# ESP32.net
KiCad netlist of a schematic drawn in Altium Designer
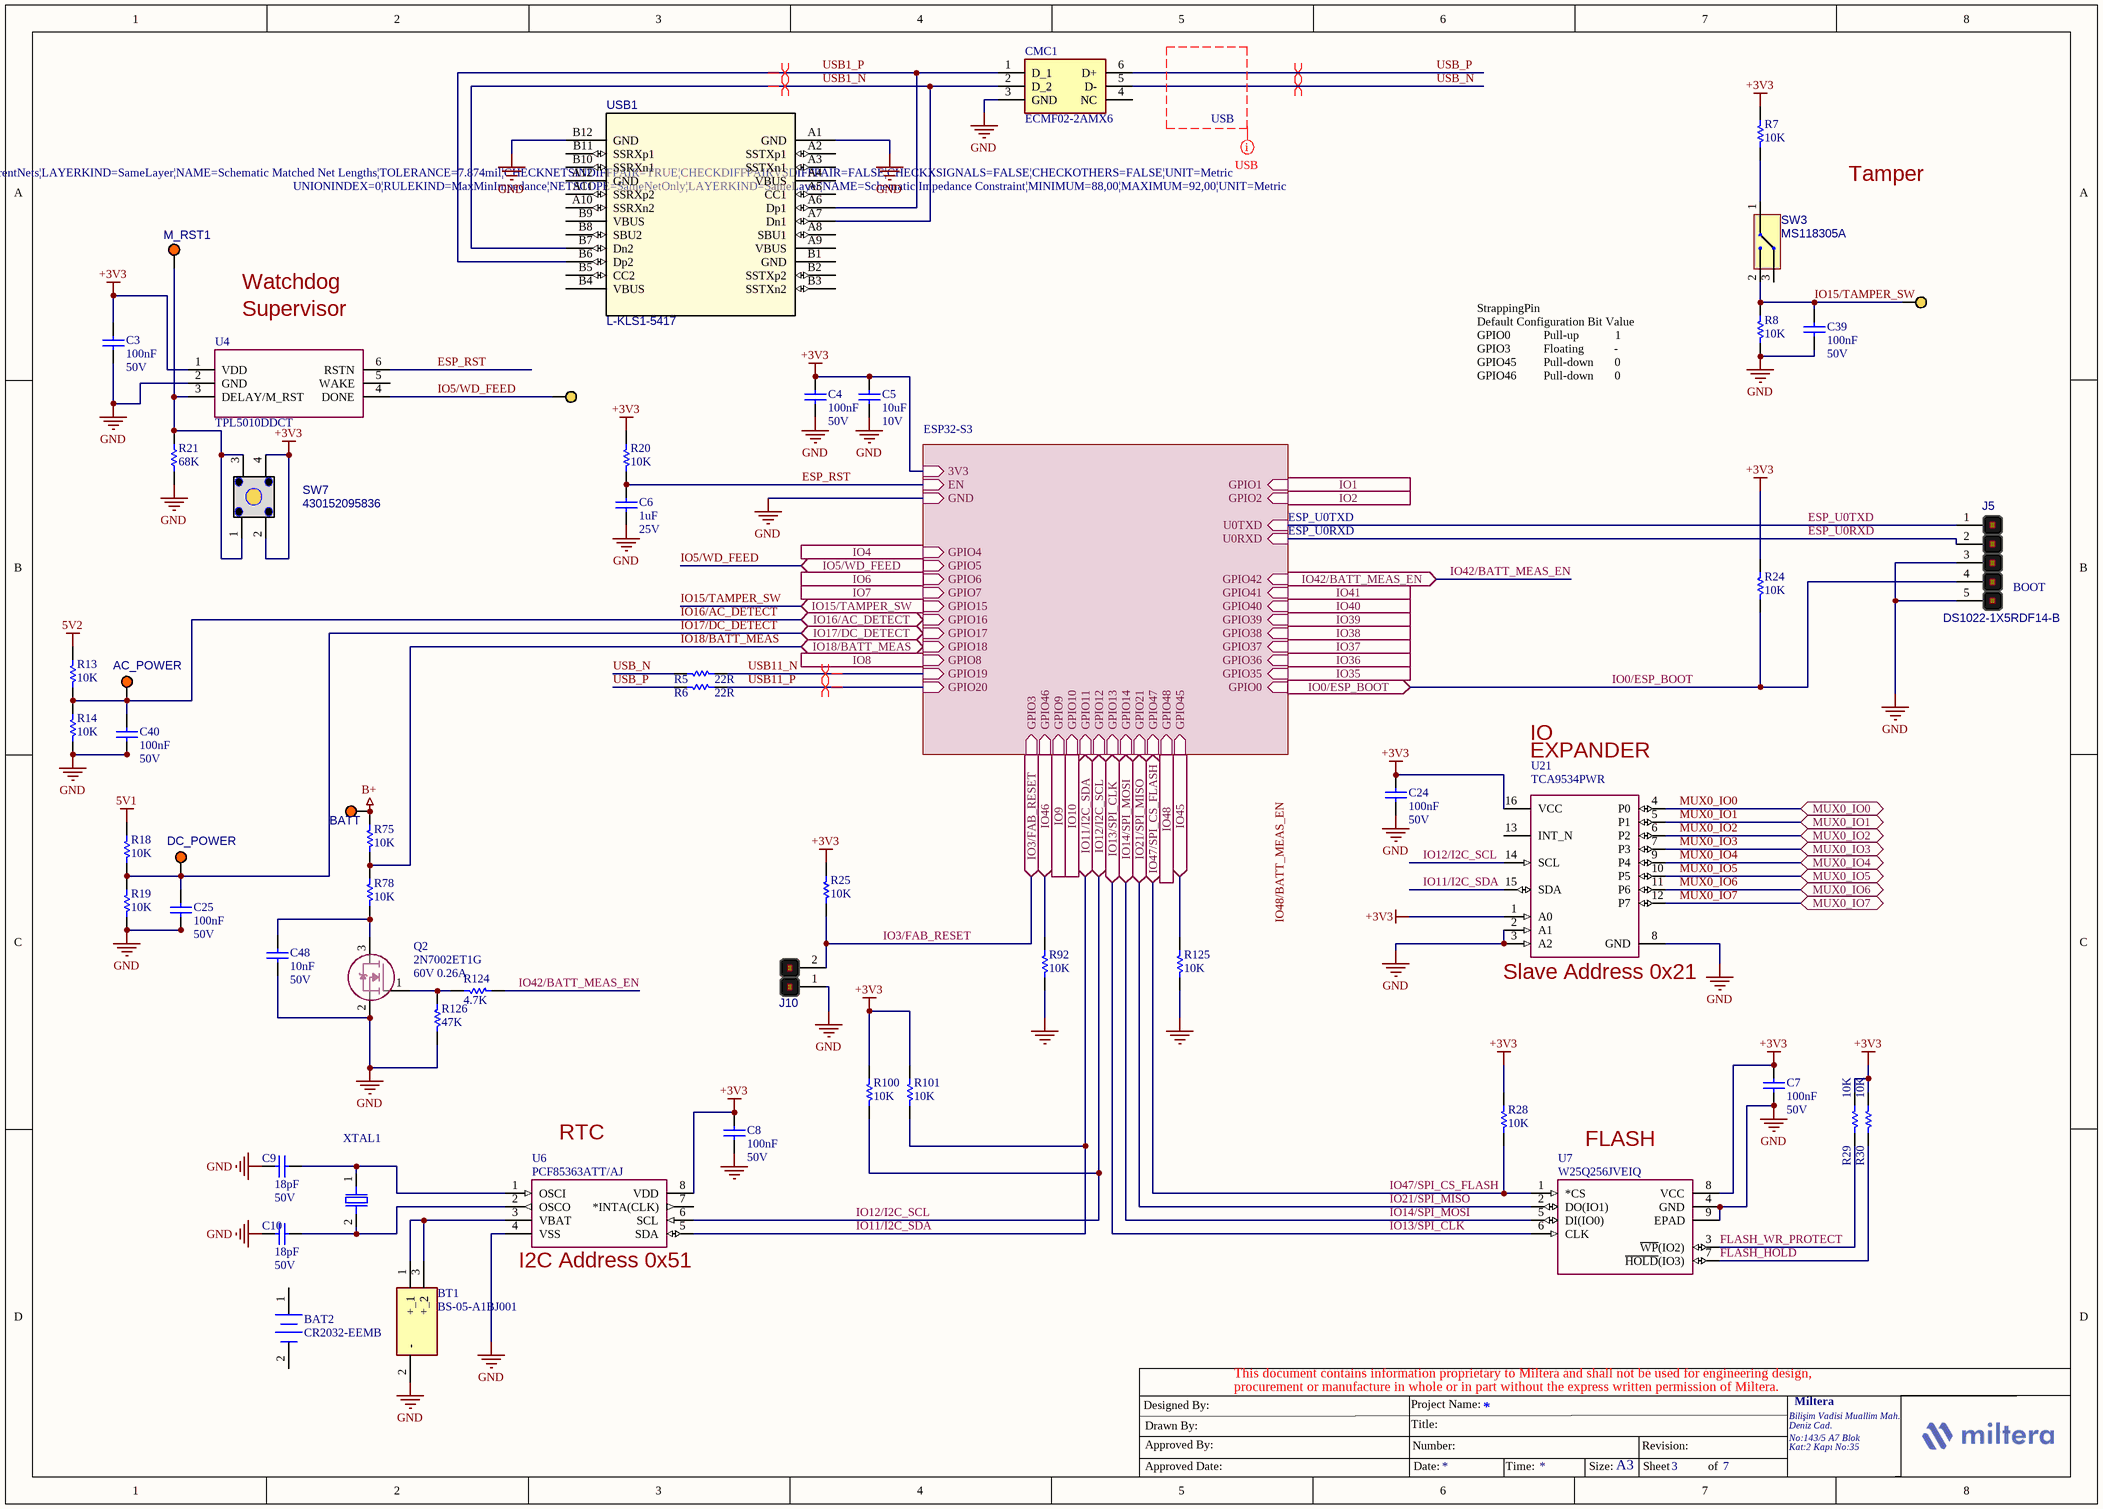
[diagram p0: ESP32.SchDoc]

(export (version "E")
  (design (tool "Eeschema 10.0.6"))
  (components
    (comp (ref "AC_POWER")
      (value "L-KLS8-TP5003")
      (footprint "TEST_POINT_ORANGE")
      (description "PC TEST POINT MINIATURE ORANGE 2.54MMX4.60MM")
      (fields (field (name "MANUFACTURER") "KLS ELECTRONIC"))
      (libsource (lib "Hardware_Fasteners") (part "5003"))
    )
    (comp (ref "BAT2")
      (value "CR2032-EEMB")
      (description "BATTERY 3V 210mA PINSIZ EEMB")
      (fields (field (name "MANUFACTURER") "EEMB"))
      (libsource (lib "open-components") (part "BAT"))
    )
    (comp (ref "BATT")
      (value "L-KLS8-TP5003")
      (footprint "TEST_POINT_ORANGE")
      (description "PC TEST POINT MINIATURE ORANGE 2.54MMX4.60MM")
      (fields (field (name "MANUFACTURER") "KLS ELECTRONIC"))
      (libsource (lib "Hardware_Fasteners") (part "5003"))
    )
    (comp (ref "BT1")
      (value "BS-05-A1BJ001")
      (footprint "SamacSys:17754851")
      (description "BATTERY HOLDER COIN CR2032 TH")
      (fields (field (name "MANUFACTURER") "MYOUNG"))
      (libsource (lib "*") (part "1775485-1"))
    )
    (comp (ref "C3")
      (value "100nF")
      (footprint "CAP_0603")
      (description "CAP CER 100nF 50VDC %10 X7R SMD")
      (fields
        (field (name "VOLTAGE") "50V")
        (field (name "MANUFACTURER") "Samsung")
        (field (name "MANUFACTURER PART NUMBER") "CL10B104KB8NNNL")
      )
      (libsource (lib "open-components") (part "CAP"))
    )
    (comp (ref "C4")
      (value "100nF")
      (footprint "CAP_0603")
      (description "CAP CER 100nF 50VDC %10 X7R SMD")
      (fields
        (field (name "VOLTAGE") "50V")
        (field (name "MANUFACTURER") "Samsung")
        (field (name "MANUFACTURER PART NUMBER") "CL10B104KB8NNNL")
      )
      (libsource (lib "open-components") (part "CAP"))
    )
    (comp (ref "C5")
      (value "10uF")
      (footprint "CAP_0603")
      (description "MLCC (1608) 0603 10uF 10VDC ±20% X5R")
      (fields
        (field (name "VOLTAGE") "10V")
        (field (name "MANUFACTURER") "Samsung")
        (field (name "MANUFACTURER PART NUMBER") "CL10A106MP8NNNC")
      )
      (libsource (lib "open-components") (part "CAP"))
    )
    (comp (ref "C6")
      (value "1uF")
      (footprint "CAP_0603")
      (description "CAP CER 1UF 25VDC %10 X5R SMD")
      (fields
        (field (name "VOLTAGE") "25V")
        (field (name "MANUFACTURER") "Samsung")
        (field (name "MANUFACTURER PART NUMBER") "CL10A105KA8NNNC")
      )
      (libsource (lib "open-components") (part "CAP"))
    )
    (comp (ref "C7")
      (value "100nF")
      (footprint "CAP_0603")
      (description "CAP CER 100nF 50VDC %10 X7R SMD")
      (fields
        (field (name "VOLTAGE") "50V")
        (field (name "MANUFACTURER") "Samsung")
        (field (name "MANUFACTURER PART NUMBER") "CL10B104KB8NNNL")
      )
      (libsource (lib "open-components") (part "CAP"))
    )
    (comp (ref "C8")
      (value "100nF")
      (footprint "CAP_0603")
      (description "CAP CER 100nF 50VDC %10 X7R SMD")
      (fields
        (field (name "VOLTAGE") "50V")
        (field (name "MANUFACTURER") "Samsung")
        (field (name "MANUFACTURER PART NUMBER") "CL10B104KB8NNNL")
      )
      (libsource (lib "open-components") (part "CAP"))
    )
    (comp (ref "C9")
      (value "18pF")
      (footprint "CAP_0603")
      (description "MLCC (1608) 0603 18pF 50VDC ±5% C0G (NP0)")
      (fields
        (field (name "VOLTAGE") "50V")
        (field (name "MANUFACTURER") "Samsung")
        (field (name "MANUFACTURER PART NUMBER") "CL10C180JB8NNNC")
      )
      (libsource (lib "open-components") (part "CAP"))
    )
    (comp (ref "C10")
      (value "18pF")
      (footprint "CAP_0603")
      (description "MLCC (1608) 0603 18pF 50VDC ±5% C0G (NP0)")
      (fields
        (field (name "VOLTAGE") "50V")
        (field (name "MANUFACTURER") "Samsung")
        (field (name "MANUFACTURER PART NUMBER") "CL10C180JB8NNNC")
      )
      (libsource (lib "open-components") (part "CAP"))
    )
    (comp (ref "C24")
      (value "100nF")
      (footprint "CAP_0603")
      (description "CAP CER 100nF 50VDC %10 X7R SMD")
      (fields
        (field (name "VOLTAGE") "50V")
        (field (name "MANUFACTURER") "Samsung")
        (field (name "MANUFACTURER PART NUMBER") "CL10B104KB8NNNL")
      )
      (libsource (lib "open-components") (part "CAP"))
    )
    (comp (ref "C25")
      (value "100nF")
      (footprint "CAP_0603")
      (description "CAP CER 100nF 50VDC %10 X7R SMD")
      (fields
        (field (name "VOLTAGE") "50V")
        (field (name "MANUFACTURER") "Samsung")
        (field (name "MANUFACTURER PART NUMBER") "CL10B104KB8NNNL")
      )
      (libsource (lib "open-components") (part "CAP"))
    )
    (comp (ref "C39")
      (value "100nF")
      (footprint "CAP_0603")
      (description "CAP CER 100nF 50VDC %10 X7R SMD")
      (fields
        (field (name "VOLTAGE") "50V")
        (field (name "MANUFACTURER") "Samsung")
        (field (name "MANUFACTURER PART NUMBER") "CL10B104KB8NNNL")
      )
      (libsource (lib "open-components") (part "CAP"))
    )
    (comp (ref "C40")
      (value "100nF")
      (footprint "CAP_0603")
      (description "CAP CER 100nF 50VDC %10 X7R SMD")
      (fields
        (field (name "VOLTAGE") "50V")
        (field (name "MANUFACTURER") "Samsung")
        (field (name "MANUFACTURER PART NUMBER") "CL10B104KB8NNNL")
      )
      (libsource (lib "open-components") (part "CAP"))
    )
    (comp (ref "C48")
      (value "10nF")
      (footprint "CAP_0603")
      (description "MLCC (1608) 0603 10nF 50VDC ±10% X7R")
      (fields
        (field (name "VOLTAGE") "50V")
        (field (name "MANUFACTURER") "SAMSUNG")
        (field (name "MANUFACTURER PART NUMBER") "CL10B103KB8NNNC")
      )
      (libsource (lib "open-components") (part "CAP"))
    )
    (comp (ref "CMC1")
      (value "ECMF02-2AMX6")
      (footprint "SamacSys:SON50P150X170X55-6N-D")
      (description "CHOKE COMMON MODE CMC 200MA 2LN 2.5 OHM SMD")
      (fields (field (name "MANUFACTURER") "STMicroelectronics"))
      (libsource (lib "*") (part "ECMF02-2AMX6"))
    )
    (comp (ref "DC_POWER")
      (value "L-KLS8-TP5003")
      (footprint "TEST_POINT_ORANGE")
      (description "PC TEST POINT MINIATURE ORANGE 2.54MMX4.60MM")
      (fields (field (name "MANUFACTURER") "KLS ELECTRONIC"))
      (libsource (lib "Hardware_Fasteners") (part "5003"))
    )
    (comp (ref "J5")
      (value "DS1022-1X5RDF14-B")
      (footprint "PIN_HEADER_MALE_TH_1x5_2.54mm")
      (description "PIN HEADER 5PIN(1x5) 2.54mm THT R/A")
      (fields (field (name "MANUFACTURER") "CONNFLY"))
      (libsource (lib "Connectors") (part "2355172-5"))
    )
    (comp (ref "J10")
      (value "L-KLS1-207-1-02-S")
      (footprint "PIN HEADER 2PIN(1x2) 2.54mm THT V/T")
      (description "PIN HEADER 2PIN(1x2) 2.54mm THT V/T")
      (fields (field (name "MANUFACTURER") "KLS ELECTRONIC"))
      (libsource (lib "MTOSOS_R02") (part "L-KLS1-207-1-02-S"))
    )
    (comp (ref "M_RST1")
      (value "L-KLS8-TP5003")
      (footprint "TEST_POINT_ORANGE")
      (description "PC TEST POINT MINIATURE ORANGE 2.54MMX4.60MM")
      (fields (field (name "MANUFACTURER") "KLS ELECTRONIC"))
      (libsource (lib "Hardware_Fasteners") (part "5003"))
    )
    (comp (ref "Q2")
      (value "2N7002ET1G")
      (footprint "SOT23")
      (description "MOSFET N-CH 60V 260mA SOT-23")
      (fields (field (name "MANUFACTURER") "On Semiconductor") (field (name "ALTIUM_VALUE") "60V 0.26A"))
      (libsource (lib "Semiconductors") (part "2N7002ET1G"))
    )
    (comp (ref "R5")
      (value "22R")
      (footprint "RES_0603")
      (description "RES 0603 22 Ohms 5% 1/10W-S 100PPM")
      (fields
        (field (name "MANUFACTURER") "ROYALOHM")
        (field (name "MANUFACTURER PART NUMBER") "0603SAJ0220T5E")
      )
      (libsource (lib "open-components") (part "RES"))
    )
    (comp (ref "R6")
      (value "22R")
      (footprint "RES_0603")
      (description "RES 0603 22 Ohms 5% 1/10W-S 100PPM")
      (fields
        (field (name "MANUFACTURER") "ROYALOHM")
        (field (name "MANUFACTURER PART NUMBER") "0603SAJ0220T5E")
      )
      (libsource (lib "open-components") (part "RES"))
    )
    (comp (ref "R7")
      (value "10K")
      (footprint "RES_0603")
      (description "RES 0603 10k Ohms %1 1/10W 100PPM")
      (fields
        (field (name "MANUFACTURER") "ROYALOHM")
        (field (name "MANUFACTURER PART NUMBER") "0603SAF1002T5E")
      )
      (libsource (lib "open-components") (part "RES"))
    )
    (comp (ref "R8")
      (value "10K")
      (footprint "RES_0603")
      (description "RES 0603 10k Ohms %1 1/10W 100PPM")
      (fields
        (field (name "MANUFACTURER") "ROYALOHM")
        (field (name "MANUFACTURER PART NUMBER") "0603SAF1002T5E")
      )
      (libsource (lib "open-components") (part "RES"))
    )
    (comp (ref "R13")
      (value "10K")
      (footprint "RES_0603")
      (description "RES 0603 10k Ohms %1 1/10W 100PPM")
      (fields
        (field (name "MANUFACTURER") "ROYALOHM")
        (field (name "MANUFACTURER PART NUMBER") "0603SAF1002T5E")
      )
      (libsource (lib "open-components") (part "RES"))
    )
    (comp (ref "R14")
      (value "10K")
      (footprint "RES_0603")
      (description "RES 0603 10k Ohms %1 1/10W 100PPM")
      (fields
        (field (name "MANUFACTURER") "ROYALOHM")
        (field (name "MANUFACTURER PART NUMBER") "0603SAF1002T5E")
      )
      (libsource (lib "open-components") (part "RES"))
    )
    (comp (ref "R18")
      (value "10K")
      (footprint "RES_0603")
      (description "RES 0603 10k Ohms %1 1/10W 100PPM")
      (fields
        (field (name "MANUFACTURER") "ROYALOHM")
        (field (name "MANUFACTURER PART NUMBER") "0603SAF1002T5E")
      )
      (libsource (lib "open-components") (part "RES"))
    )
    (comp (ref "R19")
      (value "10K")
      (footprint "RES_0603")
      (description "RES 0603 10k Ohms %1 1/10W 100PPM")
      (fields
        (field (name "MANUFACTURER") "ROYALOHM")
        (field (name "MANUFACTURER PART NUMBER") "0603SAF1002T5E")
      )
      (libsource (lib "open-components") (part "RES"))
    )
    (comp (ref "R20")
      (value "10K")
      (footprint "RES_0603")
      (description "RES 0603 10k Ohms %1 1/10W 100PPM")
      (fields
        (field (name "MANUFACTURER") "ROYALOHM")
        (field (name "MANUFACTURER PART NUMBER") "0603SAF1002T5E")
      )
      (libsource (lib "open-components") (part "RES"))
    )
    (comp (ref "R21")
      (value "68K")
      (footprint "RES_0603")
      (description "RES. 0603 68K Ohms 1% 1/10W-S 100PPM")
      (fields
        (field (name "MANUFACTURER") "ROYALOHM")
        (field (name "MANUFACTURER PART NUMBER") "0603SAF6802T5E")
      )
      (libsource (lib "open-components") (part "RES"))
    )
    (comp (ref "R24")
      (value "10K")
      (footprint "RES_0603")
      (description "RES 0603 10k Ohms %1 1/10W 100PPM")
      (fields
        (field (name "MANUFACTURER") "ROYALOHM")
        (field (name "MANUFACTURER PART NUMBER") "0603SAF1002T5E")
      )
      (libsource (lib "open-components") (part "RES"))
    )
    (comp (ref "R25")
      (value "10K")
      (footprint "RES_0603")
      (description "RES 0603 10k Ohms %1 1/10W 100PPM")
      (fields
        (field (name "MANUFACTURER") "ROYALOHM")
        (field (name "MANUFACTURER PART NUMBER") "0603SAF1002T5E")
      )
      (libsource (lib "open-components") (part "RES"))
    )
    (comp (ref "R28")
      (value "10K")
      (footprint "RES_0603")
      (description "RES 0603 10k Ohms %1 1/10W 100PPM")
      (fields
        (field (name "MANUFACTURER") "ROYALOHM")
        (field (name "MANUFACTURER PART NUMBER") "0603SAF1002T5E")
      )
      (libsource (lib "open-components") (part "RES"))
    )
    (comp (ref "R29")
      (value "10K")
      (footprint "RES_0603")
      (description "RES 0603 10k Ohms %1 1/10W 100PPM")
      (fields
        (field (name "MANUFACTURER") "ROYALOHM")
        (field (name "MANUFACTURER PART NUMBER") "0603SAF1002T5E")
      )
      (libsource (lib "open-components") (part "RES"))
    )
    (comp (ref "R30")
      (value "10K")
      (footprint "RES_0603")
      (description "RES 0603 10k Ohms %1 1/10W 100PPM")
      (fields
        (field (name "MANUFACTURER") "ROYALOHM")
        (field (name "MANUFACTURER PART NUMBER") "0603SAF1002T5E")
      )
      (libsource (lib "open-components") (part "RES"))
    )
    (comp (ref "R75")
      (value "10K")
      (footprint "RES_0603")
      (description "RES 0603 10k Ohms %1 1/10W 100PPM")
      (fields
        (field (name "MANUFACTURER") "ROYALOHM")
        (field (name "MANUFACTURER PART NUMBER") "0603SAF1002T5E")
      )
      (libsource (lib "open-components") (part "RES"))
    )
    (comp (ref "R78")
      (value "10K")
      (footprint "RES_0603")
      (description "RES 0603 10k Ohms %1 1/10W 100PPM")
      (fields
        (field (name "MANUFACTURER") "ROYALOHM")
        (field (name "MANUFACTURER PART NUMBER") "0603SAF1002T5E")
      )
      (libsource (lib "open-components") (part "RES"))
    )
    (comp (ref "R92")
      (value "10K")
      (footprint "RES_0603")
      (description "RES 0603 10k Ohms %1 1/10W 100PPM")
      (fields
        (field (name "MANUFACTURER") "ROYALOHM")
        (field (name "MANUFACTURER PART NUMBER") "0603SAF1002T5E")
      )
      (libsource (lib "open-components") (part "RES"))
    )
    (comp (ref "R100")
      (value "10K")
      (footprint "RES_0603")
      (description "RES 0603 10k Ohms %1 1/10W 100PPM")
      (fields
        (field (name "MANUFACTURER") "ROYALOHM")
        (field (name "MANUFACTURER PART NUMBER") "0603SAF1002T5E")
      )
      (libsource (lib "open-components") (part "RES"))
    )
    (comp (ref "R101")
      (value "10K")
      (footprint "RES_0603")
      (description "RES 0603 10k Ohms %1 1/10W 100PPM")
      (fields
        (field (name "MANUFACTURER") "ROYALOHM")
        (field (name "MANUFACTURER PART NUMBER") "0603SAF1002T5E")
      )
      (libsource (lib "open-components") (part "RES"))
    )
    (comp (ref "R124")
      (value "4.7K")
      (footprint "RES_0603")
      (description "RES 0603 4.7k Ohms %1 1/10W 100PPM")
      (fields
        (field (name "MANUFACTURER") "ROYALOHM")
        (field (name "MANUFACTURER PART NUMBER") "0603SAF4701T5E")
      )
      (libsource (lib "open-components") (part "RES"))
    )
    (comp (ref "R125")
      (value "10K")
      (footprint "RES_0603")
      (description "RES 0603 10k Ohms %1 1/10W 100PPM")
      (fields
        (field (name "MANUFACTURER") "ROYALOHM")
        (field (name "MANUFACTURER PART NUMBER") "0603SAF1002T5E")
      )
      (libsource (lib "open-components") (part "RES"))
    )
    (comp (ref "R126")
      (value "47K")
      (footprint "RES_0603")
      (description "RES 0603 47K Ohms 1% 1/10W-S 100PPM")
      (fields
        (field (name "MANUFACTURER") "ROYALOHM")
        (field (name "MANUFACTURER PART NUMBER") "0603SAF4702T5E")
      )
      (libsource (lib "open-components") (part "RES"))
    )
    (comp (ref "SW3")
      (value "MS118305A")
      (footprint "MS118305A")
      (description "SWITCH MICRO SPDT 100mA 30VDC 25gF")
      (fields (field (name "MANUFACTURER") "LITTELFUSE-C&K"))
      (libsource (lib "Schlib1") (part "MS118305A"))
    )
    (comp (ref "SW7")
      (value "430152095836")
      (footprint "SMD_TACT_SW_6x6_9.50mm")
      (description "SWITCH TACT 6.2x6.2 9.50mm 360gF SMT V/T")
      (fields (field (name "MANUFACTURER") "Würth Elektronik"))
      (libsource (lib "Electromechanical") (part "430152095836"))
    )
    (comp (ref "TAMPER_SW")
      (value "L-KLS8-TP5004")
      (footprint "TEST_POINT_YELLOW")
      (description "PC TEST POINT MINIATURE YELLOW 2.54MMX4.60MM")
      (fields (field (name "MANUFACTURER") "KLS ELECTRONIC"))
      (libsource (lib "Hardware_Fasteners") (part "5004"))
    )
    (comp (ref "U4")
      (value "TPL5010DDCT")
      (footprint "SOT95P280X110-6N")
      (description "IC OSC PROG TIMER TSOT23-6")
      (fields (field (name "MANUFACTURER") "Texas Instruments"))
      (libsource (lib "Schlib1") (part "TPL5010DDCT"))
    )
    (comp (ref "U6")
      (value "PCF85363ATT/AJ")
      (footprint "TSSOP8_SOT505-1_NXP")
      (description "IC RTC CLK/CALENDAR I2C 8TSSOP")
      (fields (field (name "MANUFACTURER") "NXP USA Inc."))
      (libsource (lib "Schlib1") (part "PCF85363ATT/AJ"))
    )
    (comp (ref "U7")
      (value "W25Q256JVEIQ")
      (footprint "8-WSON (8x6)")
      (description "IC FLASH 256MBIT SPI/QUAD 8WSON")
      (fields (field (name "MANUFACTURER") "Winbond Electronics"))
      (libsource (lib "Schlib1") (part "W25Q256JVEIQ"))
    )
    (comp (ref "U21")
      (value "TCA9534PWR")
      (footprint "16-TSSOP")
      (description "IC XPNDR 400KHZ I2C 16TSSOP")
      (fields (field (name "MANUFACTURER") "Texas Instruments"))
      (libsource (lib "Schlib1") (part "TCA9534PWR"))
    )
    (comp (ref "USB1")
      (value "L-KLS1-5417")
      (footprint "217C-AA01_ATT")
      (description "CONNECTOR USB 14P USB FEMALE SOCKET C TYPE")
      (fields (field (name "MANUFACTURER") "KLS ELECTRONIC"))
      (libsource (lib "MTOSOS_R02") (part "L-KLS1-5461"))
    )
    (comp (ref "WD_FEED1")
      (value "L-KLS8-TP5004")
      (footprint "TEST_POINT_YELLOW")
      (description "PC TEST POINT MINIATURE YELLOW 2.54MMX4.60MM")
      (fields (field (name "MANUFACTURER") "KLS ELECTRONIC"))
      (libsource (lib "Hardware_Fasteners") (part "5004"))
    )
    (comp (ref "XTAL1")
      (value "Crystal_2pin")
      (footprint "XTAL_3x8")
      (description "CRYSTAL 32.768KHZ 12.5PF 5ppm 3x8")
      (fields
        (field (name "MANUFACTURER PART NUMBER") "R38-32.768-12.5-EXT-5PPM")
        (field (name "MANUFACTURER") "Raltron")
      )
      (libsource (lib "open-components") (part "Crystal_2pin"))
    )
  )
  (nets
    (net (code "1") (name "+3V3") (class "Default")
      (node (ref "C24") (pin "1") (pinfunction "1_1") (pintype "passive"))
      (node (ref "C3") (pin "1") (pinfunction "1_1") (pintype "passive"))
      (node (ref "C4") (pin "1") (pinfunction "1_1") (pintype "passive"))
      (node (ref "C5") (pin "1") (pinfunction "1_1") (pintype "passive"))
      (node (ref "C7") (pin "1") (pinfunction "1_1") (pintype "passive"))
      (node (ref "C8") (pin "1") (pinfunction "1_1") (pintype "passive"))
      (node (ref "R100") (pin "1") (pinfunction "1_1") (pintype "passive"))
      (node (ref "R101") (pin "1") (pinfunction "1_1") (pintype "passive"))
      (node (ref "R20") (pin "1") (pinfunction "1_1") (pintype "passive"))
      (node (ref "R24") (pin "1") (pinfunction "1_1") (pintype "passive"))
      (node (ref "R25") (pin "1") (pinfunction "1_1") (pintype "passive"))
      (node (ref "R28") (pin "1") (pinfunction "1_1") (pintype "passive"))
      (node (ref "R29") (pin "1") (pinfunction "1_1") (pintype "passive"))
      (node (ref "R30") (pin "1") (pinfunction "1_1") (pintype "passive"))
      (node (ref "R7") (pin "1") (pinfunction "1_1") (pintype "passive"))
      (node (ref "SW7") (pin "2") (pinfunction "2_2") (pintype "passive"))
      (node (ref "SW7") (pin "4") (pinfunction "4_4") (pintype "passive"))
      (node (ref "U21") (pin "1") (pinfunction "A0_1") (pintype "input"))
      (node (ref "U21") (pin "16") (pinfunction "VCC_16") (pintype "power_in"))
      (node (ref "U4") (pin "1") (pinfunction "VDD_1") (pintype "passive"))
      (node (ref "U6") (pin "8") (pinfunction "VDD_8") (pintype "power_in"))
      (node (ref "U7") (pin "8") (pinfunction "VCC_8") (pintype "power_in"))
    )
    (net (code "2") (name "/ESP_RST") (class "Default")
      (node (ref "C6") (pin "1") (pinfunction "1_1") (pintype "passive"))
      (node (ref "R20") (pin "2") (pinfunction "2_2") (pintype "passive"))
      (node (ref "U4") (pin "6") (pinfunction "RSTN_6") (pintype "passive"))
    )
    (net (code "3") (name "/ESP_U0RXD") (class "Default")
      (node (ref "J5") (pin "2") (pinfunction "2_2") (pintype "passive"))
    )
    (net (code "4") (name "/ESP_U0TXD") (class "Default")
      (node (ref "J5") (pin "1") (pinfunction "1_1") (pintype "passive"))
    )
    (net (code "5") (name "/FLASH_HOLD") (class "Default")
      (node (ref "R30") (pin "2") (pinfunction "2_2") (pintype "passive"))
      (node (ref "U7") (pin "7") (pinfunction "~{HOLD}(IO3)_7") (pintype "bidirectional"))
    )
    (net (code "6") (name "/FLASH_WR_PROTECT") (class "Default")
      (node (ref "R29") (pin "2") (pinfunction "2_2") (pintype "passive"))
      (node (ref "U7") (pin "3") (pinfunction "~{WP}(IO2)_3") (pintype "bidirectional"))
    )
    (net (code "7") (name "/IO0{slash}ESP_BOOT") (class "Default")
      (node (ref "J5") (pin "4") (pinfunction "4_4") (pintype "passive"))
      (node (ref "R24") (pin "2") (pinfunction "2_2") (pintype "passive"))
    )
    (net (code "10") (name "/IO3{slash}FAB_RESET") (class "Default")
      (node (ref "J10") (pin "2") (pinfunction "2_2") (pintype "passive"))
      (node (ref "R25") (pin "2") (pinfunction "2_2") (pintype "passive"))
    )
    (net (code "12") (name "/IO5{slash}WD_FEED") (class "Default")
      (node (ref "U4") (pin "4") (pinfunction "DONE_4") (pintype "passive"))
      (node (ref "WD_FEED1") (pin "1") (pintype "passive"))
    )
    (net (code "18") (name "/IO11{slash}I2C_SDA") (class "Default")
      (node (ref "R101") (pin "2") (pinfunction "2_2") (pintype "passive"))
      (node (ref "U21") (pin "15") (pinfunction "SDA_15") (pintype "bidirectional"))
      (node (ref "U6") (pin "5") (pinfunction "SDA_5") (pintype "bidirectional"))
    )
    (net (code "19") (name "/IO12{slash}I2C_SCL") (class "Default")
      (node (ref "R100") (pin "2") (pinfunction "2_2") (pintype "passive"))
      (node (ref "U21") (pin "14") (pinfunction "SCL_14") (pintype "input"))
      (node (ref "U6") (pin "6") (pinfunction "SCL_6") (pintype "input"))
    )
    (net (code "20") (name "/IO13{slash}SPI_CLK") (class "Default")
      (node (ref "U7") (pin "6") (pinfunction "CLK_6") (pintype "input"))
    )
    (net (code "21") (name "/IO14{slash}SPI_MOSI") (class "Default")
      (node (ref "U7") (pin "5") (pinfunction "DI(IO0)_5") (pintype "bidirectional"))
    )
    (net (code "22") (name "/IO15{slash}TAMPER_SW") (class "Default")
      (node (ref "C39") (pin "1") (pinfunction "1_1") (pintype "passive"))
      (node (ref "R8") (pin "1") (pinfunction "1_1") (pintype "passive"))
      (node (ref "SW3") (pin "2") (pinfunction "2_2") (pintype "passive"))
      (node (ref "TAMPER_SW") (pin "1") (pintype "passive"))
    )
    (net (code "23") (name "/IO16{slash}AC_DETECT") (class "Default")
      (node (ref "AC_POWER") (pin "1") (pintype "passive"))
      (node (ref "C40") (pin "1") (pinfunction "1_1") (pintype "passive"))
      (node (ref "R13") (pin "2") (pinfunction "2_2") (pintype "passive"))
      (node (ref "R14") (pin "1") (pinfunction "1_1") (pintype "passive"))
    )
    (net (code "24") (name "/IO17{slash}DC_DETECT") (class "Default")
      (node (ref "C25") (pin "1") (pinfunction "1_1") (pintype "passive"))
      (node (ref "DC_POWER") (pin "1") (pintype "passive"))
      (node (ref "R18") (pin "2") (pinfunction "2_2") (pintype "passive"))
      (node (ref "R19") (pin "1") (pinfunction "1_1") (pintype "passive"))
    )
    (net (code "25") (name "/IO18{slash}BATT_MEAS") (class "Default")
      (node (ref "R75") (pin "2") (pinfunction "2_2") (pintype "passive"))
      (node (ref "R78") (pin "1") (pinfunction "1_1") (pintype "passive"))
    )
    (net (code "26") (name "/IO21{slash}SPI_MISO") (class "Default")
      (node (ref "U7") (pin "2") (pinfunction "DO(IO1)_2") (pintype "bidirectional"))
    )
    (net (code "34") (name "/IO42{slash}BATT_MEAS_EN") (class "Default")
      (node (ref "R124") (pin "1") (pinfunction "1_1") (pintype "passive"))
    )
    (net (code "35") (name "/IO45") (class "Default")
      (node (ref "R125") (pin "1") (pinfunction "1_1") (pintype "passive"))
    )
    (net (code "36") (name "/IO46") (class "Default")
      (node (ref "R92") (pin "1") (pinfunction "1_1") (pintype "passive"))
    )
    (net (code "37") (name "/IO47{slash}SPI_CS_FLASH") (class "Default")
      (node (ref "R28") (pin "2") (pinfunction "2_2") (pintype "passive"))
      (node (ref "U7") (pin "1") (pinfunction "*CS_1") (pintype "input"))
    )
    (net (code "40") (name "/MUX0_IO0") (class "Default")
      (node (ref "U21") (pin "4") (pinfunction "P0_4") (pintype "bidirectional"))
    )
    (net (code "41") (name "/MUX0_IO1") (class "Default")
      (node (ref "U21") (pin "5") (pinfunction "P1_5") (pintype "bidirectional"))
    )
    (net (code "42") (name "/MUX0_IO2") (class "Default")
      (node (ref "U21") (pin "6") (pinfunction "P2_6") (pintype "bidirectional"))
    )
    (net (code "43") (name "/MUX0_IO3") (class "Default")
      (node (ref "U21") (pin "7") (pinfunction "P3_7") (pintype "bidirectional"))
    )
    (net (code "44") (name "/MUX0_IO4") (class "Default")
      (node (ref "U21") (pin "9") (pinfunction "P4_9") (pintype "bidirectional"))
    )
    (net (code "45") (name "/MUX0_IO5") (class "Default")
      (node (ref "U21") (pin "10") (pinfunction "P5_10") (pintype "bidirectional"))
    )
    (net (code "46") (name "/MUX0_IO6") (class "Default")
      (node (ref "U21") (pin "11") (pinfunction "P6_11") (pintype "bidirectional"))
    )
    (net (code "47") (name "/MUX0_IO7") (class "Default")
      (node (ref "U21") (pin "12") (pinfunction "P7_12") (pintype "bidirectional"))
    )
    (net (code "48") (name "/USB1_N") (class "Default")
      (node (ref "CMC1") (pin "2") (pinfunction "D_2_2") (pintype "passive"))
      (node (ref "USB1") (pin "A7") (pinfunction "Dn1_A7") (pintype "bidirectional"))
      (node (ref "USB1") (pin "B7") (pinfunction "Dn2_B7") (pintype "bidirectional"))
    )
    (net (code "49") (name "/USB1_P") (class "Default")
      (node (ref "CMC1") (pin "1") (pinfunction "D_1_1") (pintype "passive"))
      (node (ref "USB1") (pin "A6") (pinfunction "Dp1_A6") (pintype "bidirectional"))
      (node (ref "USB1") (pin "B6") (pinfunction "Dp2_B6") (pintype "bidirectional"))
    )
    (net (code "50") (name "/USB11_N") (class "Default")
      (node (ref "R5") (pin "2") (pinfunction "2_2") (pintype "passive"))
    )
    (net (code "51") (name "/USB11_P") (class "Default")
      (node (ref "R6") (pin "2") (pinfunction "2_2") (pintype "passive"))
    )
    (net (code "52") (name "/USB_N") (class "Default")
      (node (ref "CMC1") (pin "5") (pinfunction "D-_5") (pintype "passive"))
      (node (ref "R5") (pin "1") (pinfunction "1_1") (pintype "passive"))
    )
    (net (code "53") (name "/USB_P") (class "Default")
      (node (ref "CMC1") (pin "6") (pinfunction "D+_6") (pintype "passive"))
      (node (ref "R6") (pin "1") (pinfunction "1_1") (pintype "passive"))
    )
    (net (code "54") (name "5V1") (class "Default")
      (node (ref "R18") (pin "1") (pinfunction "1_1") (pintype "passive"))
    )
    (net (code "55") (name "5V2") (class "Default")
      (node (ref "R13") (pin "1") (pinfunction "1_1") (pintype "passive"))
    )
    (net (code "56") (name "B+") (class "Default")
      (node (ref "BATT") (pin "1") (pintype "passive"))
      (node (ref "R75") (pin "1") (pinfunction "1_1") (pintype "passive"))
    )
    (net (code "57") (name "GND") (class "Default")
      (node (ref "BT1") (pin "2") (pinfunction "-_2") (pintype "passive"))
      (node (ref "C10") (pin "1") (pinfunction "1_1") (pintype "passive"))
      (node (ref "C24") (pin "2") (pinfunction "2_2") (pintype "passive"))
      (node (ref "C25") (pin "2") (pinfunction "2_2") (pintype "passive"))
      (node (ref "C3") (pin "2") (pinfunction "2_2") (pintype "passive"))
      (node (ref "C39") (pin "2") (pinfunction "2_2") (pintype "passive"))
      (node (ref "C4") (pin "2") (pinfunction "2_2") (pintype "passive"))
      (node (ref "C40") (pin "2") (pinfunction "2_2") (pintype "passive"))
      (node (ref "C48") (pin "2") (pinfunction "2_2") (pintype "passive"))
      (node (ref "C5") (pin "2") (pinfunction "2_2") (pintype "passive"))
      (node (ref "C6") (pin "2") (pinfunction "2_2") (pintype "passive"))
      (node (ref "C7") (pin "2") (pinfunction "2_2") (pintype "passive"))
      (node (ref "C8") (pin "2") (pinfunction "2_2") (pintype "passive"))
      (node (ref "C9") (pin "1") (pinfunction "1_1") (pintype "passive"))
      (node (ref "CMC1") (pin "3") (pinfunction "GND_3") (pintype "passive"))
      (node (ref "J10") (pin "1") (pinfunction "1_1") (pintype "passive"))
      (node (ref "J5") (pin "3") (pinfunction "3_3") (pintype "passive"))
      (node (ref "J5") (pin "5") (pinfunction "5_5") (pintype "passive"))
      (node (ref "Q2") (pin "2") (pinfunction "S_2") (pintype "passive"))
      (node (ref "R125") (pin "2") (pinfunction "2_2") (pintype "passive"))
      (node (ref "R126") (pin "2") (pinfunction "2_2") (pintype "passive"))
      (node (ref "R14") (pin "2") (pinfunction "2_2") (pintype "passive"))
      (node (ref "R19") (pin "2") (pinfunction "2_2") (pintype "passive"))
      (node (ref "R21") (pin "2") (pinfunction "2_2") (pintype "passive"))
      (node (ref "R8") (pin "2") (pinfunction "2_2") (pintype "passive"))
      (node (ref "R92") (pin "2") (pinfunction "2_2") (pintype "passive"))
      (node (ref "U21") (pin "2") (pinfunction "A1_2") (pintype "input"))
      (node (ref "U21") (pin "3") (pinfunction "A2_3") (pintype "input"))
      (node (ref "U21") (pin "8") (pinfunction "GND_8") (pintype "power_in"))
      (node (ref "U4") (pin "2") (pinfunction "GND_2") (pintype "passive"))
      (node (ref "U6") (pin "4") (pinfunction "VSS_4") (pintype "power_in"))
      (node (ref "U7") (pin "4") (pinfunction "GND_4") (pintype "power_in"))
      (node (ref "U7") (pin "9") (pinfunction "EPAD_9") (pintype "passive"))
      (node (ref "USB1") (pin "A1") (pinfunction "GND_A1") (pintype "power_in"))
      (node (ref "USB1") (pin "B12") (pinfunction "GND_B12") (pintype "power_in"))
    )
    (net (code "58") (name "Net-(BT1-+_1)") (class "Default")
      (node (ref "BT1") (pin "1") (pinfunction "+_1_1") (pintype "passive"))
      (node (ref "BT1") (pin "3") (pinfunction "+_2_3") (pintype "passive"))
      (node (ref "U6") (pin "3") (pinfunction "VBAT_3") (pintype "power_in"))
    )
    (net (code "59") (name "Net-(Q2-D)") (class "Default")
      (node (ref "C48") (pin "1") (pinfunction "1_1") (pintype "passive"))
      (node (ref "Q2") (pin "3") (pinfunction "D_3") (pintype "passive"))
      (node (ref "R78") (pin "2") (pinfunction "2_2") (pintype "passive"))
    )
    (net (code "60") (name "Net-(Q2-G)") (class "Default")
      (node (ref "Q2") (pin "1") (pinfunction "G_1") (pintype "passive"))
      (node (ref "R124") (pin "2") (pinfunction "2_2") (pintype "passive"))
      (node (ref "R126") (pin "1") (pinfunction "1_1") (pintype "passive"))
    )
    (net (code "61") (name "Net-(R7-Pad2)") (class "Default")
      (node (ref "R7") (pin "2") (pinfunction "2_2") (pintype "passive"))
      (node (ref "SW3") (pin "1") (pinfunction "1_1") (pintype "passive"))
    )
    (net (code "62") (name "Net-(U4-DELAY{slash}M_RST)") (class "Default")
      (node (ref "M_RST1") (pin "1") (pintype "passive"))
      (node (ref "R21") (pin "1") (pinfunction "1_1") (pintype "passive"))
      (node (ref "SW7") (pin "1") (pinfunction "1_1") (pintype "passive"))
      (node (ref "SW7") (pin "3") (pinfunction "3_3") (pintype "passive"))
      (node (ref "U4") (pin "3") (pinfunction "DELAY/M_RST_3") (pintype "passive"))
    )
    (net (code "63") (name "Net-(U6-OSCI)") (class "Default")
      (node (ref "C9") (pin "2") (pinfunction "2_2") (pintype "passive"))
      (node (ref "U6") (pin "1") (pinfunction "OSCI_1") (pintype "input"))
      (node (ref "XTAL1") (pin "1") (pintype "passive"))
    )
    (net (code "64") (name "Net-(U6-OSCO)") (class "Default")
      (node (ref "C10") (pin "2") (pinfunction "2_2") (pintype "passive"))
      (node (ref "U6") (pin "2") (pinfunction "OSCO_2") (pintype "output"))
      (node (ref "XTAL1") (pin "2") (pintype "passive"))
    )
    (net (code "65") (name "unconnected-(BAT2-+-Pad1)") (class "Default")
      (node (ref "BAT2") (pin "1") (pinfunction "+_1") (pintype "passive"))
    )
    (net (code "66") (name "unconnected-(BAT2---Pad2)") (class "Default")
      (node (ref "BAT2") (pin "2") (pinfunction "-_2") (pintype "passive"))
    )
    (net (code "67") (name "unconnected-(CMC1-NC-Pad4)") (class "Default")
      (node (ref "CMC1") (pin "4") (pinfunction "NC_4") (pintype "passive"))
    )
    (net (code "68") (name "unconnected-(SW3-Pad3)") (class "Default")
      (node (ref "SW3") (pin "3") (pinfunction "3_3") (pintype "passive"))
    )
    (net (code "69") (name "unconnected-(U4-WAKE-Pad5)") (class "Default")
      (node (ref "U4") (pin "5") (pinfunction "WAKE_5") (pintype "passive"))
    )
    (net (code "70") (name "unconnected-(U6-*INTA(CLK)-Pad7)") (class "Default")
      (node (ref "U6") (pin "7") (pinfunction "*INTA(CLK)_7") (pintype "output"))
    )
    (net (code "71") (name "unconnected-(U21-INT_N-Pad13)") (class "Default")
      (node (ref "U21") (pin "13") (pinfunction "INT_N_13") (pintype "open_collector"))
    )
    (net (code "72") (name "unconnected-(USB1-CC1-PadA5)") (class "Default")
      (node (ref "USB1") (pin "A5") (pinfunction "CC1_A5") (pintype "bidirectional"))
    )
    (net (code "73") (name "unconnected-(USB1-CC2-PadB5)") (class "Default")
      (node (ref "USB1") (pin "B5") (pinfunction "CC2_B5") (pintype "bidirectional"))
    )
    (net (code "74") (name "unconnected-(USB1-GND-PadA12)") (class "Default")
      (node (ref "USB1") (pin "A12") (pinfunction "GND_A12") (pintype "power_in"))
    )
    (net (code "75") (name "unconnected-(USB1-GND-PadB1)") (class "Default")
      (node (ref "USB1") (pin "B1") (pinfunction "GND_B1") (pintype "power_in"))
    )
    (net (code "76") (name "unconnected-(USB1-SBU1-PadA8)") (class "Default")
      (node (ref "USB1") (pin "A8") (pinfunction "SBU1_A8") (pintype "bidirectional"))
    )
    (net (code "77") (name "unconnected-(USB1-SBU2-PadB8)") (class "Default")
      (node (ref "USB1") (pin "B8") (pinfunction "SBU2_B8") (pintype "bidirectional"))
    )
    (net (code "78") (name "unconnected-(USB1-SSRXn1-PadB10)") (class "Default")
      (node (ref "USB1") (pin "B10") (pinfunction "SSRXn1_B10") (pintype "bidirectional"))
    )
    (net (code "79") (name "unconnected-(USB1-SSRXn2-PadA10)") (class "Default")
      (node (ref "USB1") (pin "A10") (pinfunction "SSRXn2_A10") (pintype "bidirectional"))
    )
    (net (code "80") (name "unconnected-(USB1-SSRXp1-PadB11)") (class "Default")
      (node (ref "USB1") (pin "B11") (pinfunction "SSRXp1_B11") (pintype "bidirectional"))
    )
    (net (code "81") (name "unconnected-(USB1-SSRXp2-PadA11)") (class "Default")
      (node (ref "USB1") (pin "A11") (pinfunction "SSRXp2_A11") (pintype "bidirectional"))
    )
    (net (code "82") (name "unconnected-(USB1-SSTXn1-PadA3)") (class "Default")
      (node (ref "USB1") (pin "A3") (pinfunction "SSTXn1_A3") (pintype "bidirectional"))
    )
    (net (code "83") (name "unconnected-(USB1-SSTXn2-PadB3)") (class "Default")
      (node (ref "USB1") (pin "B3") (pinfunction "SSTXn2_B3") (pintype "bidirectional"))
    )
    (net (code "84") (name "unconnected-(USB1-SSTXp1-PadA2)") (class "Default")
      (node (ref "USB1") (pin "A2") (pinfunction "SSTXp1_A2") (pintype "bidirectional"))
    )
    (net (code "85") (name "unconnected-(USB1-SSTXp2-PadB2)") (class "Default")
      (node (ref "USB1") (pin "B2") (pinfunction "SSTXp2_B2") (pintype "bidirectional"))
    )
    (net (code "86") (name "unconnected-(USB1-VBUS-PadA4)") (class "Default")
      (node (ref "USB1") (pin "A4") (pinfunction "VBUS_A4") (pintype "power_in"))
    )
    (net (code "87") (name "unconnected-(USB1-VBUS-PadA9)") (class "Default")
      (node (ref "USB1") (pin "A9") (pinfunction "VBUS_A9") (pintype "power_in"))
    )
    (net (code "88") (name "unconnected-(USB1-VBUS-PadB4)") (class "Default")
      (node (ref "USB1") (pin "B4") (pinfunction "VBUS_B4") (pintype "power_in"))
    )
    (net (code "89") (name "unconnected-(USB1-VBUS-PadB9)") (class "Default")
      (node (ref "USB1") (pin "B9") (pinfunction "VBUS_B9") (pintype "power_in"))
    )
  )
)
